# Sheet3.net
KiCad netlist of a schematic drawn in Altium Designer
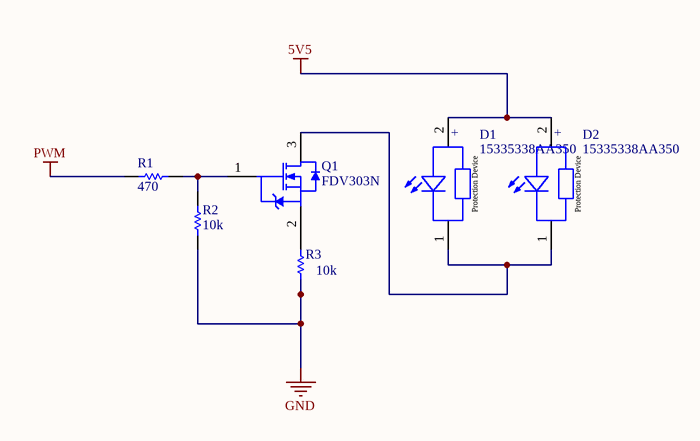
[diagram p0: Sheet3.SchDoc]

(export (version "E")
  (design (tool "Eeschema 10.0.6"))
  (components
    (comp (ref "D1")
      (value "15335338AA350")
      (footprint "WL-SUMW_3535 UV-A_L3.4W3.4H2.1")
      (description "15335338AA350 WL-SUMW SMT UltraViolet Ceramic Waterclear")
      (libsource (lib "Altium Content Vault") (part "WL-SUMW"))
    )
    (comp (ref "D2")
      (value "15335338AA350")
      (footprint "WL-SUMW_3535 UV-A_L3.4W3.4H2.1")
      (description "15335338AA350 WL-SUMW SMT UltraViolet Ceramic Waterclear")
      (libsource (lib "Altium Content Vault") (part "WL-SUMW"))
    )
    (comp (ref "Q1")
      (value "FDV303N")
      (footprint "FAIR-FDV303N-3_V")
      (fields (field (name "MANUFACTURER") "Fairchild"))
      (libsource (lib "Altium Content Vault") (part "NEMOS-GSD-3_D"))
    )
    (comp (ref "R1")
      (value "470")
      (footprint "RESC1609X50X30NL8T20")
      (description "Chip Resistor, 0 Ohm, Jumper, 100 mW, -55 to 155 degC, 0603 (1608 Metric), RoHS, Tape and Reel")
      (fields (field (name "MANUFACTURER") "Vishay Semiconductor"))
      (libsource (lib "Altium Content Vault") (part "RES-2"))
    )
    (comp (ref "R2")
      (value "10k")
      (footprint "RESC1609X50X30NL8T20")
      (description "Chip Resistor, 0 Ohm, Jumper, 100 mW, -55 to 155 degC, 0603 (1608 Metric), RoHS, Tape and Reel")
      (fields (field (name "MANUFACTURER") "Vishay Semiconductor"))
      (libsource (lib "Altium Content Vault") (part "RES-2"))
    )
    (comp (ref "R3")
      (value "10k")
      (footprint "RESC1609X50X30NL8T20")
      (description "Chip Resistor, 0 Ohm, Jumper, 100 mW, -55 to 155 degC, 0603 (1608 Metric), RoHS, Tape and Reel")
      (fields (field (name "MANUFACTURER") "Vishay Semiconductor"))
      (libsource (lib "Altium Content Vault") (part "RES-2"))
    )
  )
  (nets
    (net (code "1") (name "5V5") (class "Default")
      (node (ref "D1") (pin "2") (pinfunction "A_2") (pintype "passive"))
      (node (ref "D2") (pin "2") (pinfunction "A_2") (pintype "passive"))
    )
    (net (code "2") (name "GND") (class "Default")
      (node (ref "R2") (pin "1") (pinfunction "1_1") (pintype "passive"))
      (node (ref "R3") (pin "1") (pinfunction "1_1") (pintype "passive"))
    )
    (net (code "3") (name "Net-(D1-K)") (class "Default")
      (node (ref "D1") (pin "1") (pinfunction "K_1") (pintype "passive"))
      (node (ref "D2") (pin "1") (pinfunction "K_1") (pintype "passive"))
      (node (ref "Q1") (pin "3") (pinfunction "D_3") (pintype "passive"))
    )
    (net (code "4") (name "Net-(Q1-G)") (class "Default")
      (node (ref "Q1") (pin "1") (pinfunction "G_1") (pintype "passive"))
      (node (ref "R1") (pin "2") (pinfunction "2_2") (pintype "passive"))
      (node (ref "R2") (pin "2") (pinfunction "2_2") (pintype "passive"))
    )
    (net (code "5") (name "Net-(Q1-S)") (class "Default")
      (node (ref "Q1") (pin "2") (pinfunction "S_2") (pintype "passive"))
      (node (ref "R3") (pin "2") (pinfunction "2_2") (pintype "passive"))
    )
    (net (code "6") (name "PWM") (class "Default")
      (node (ref "R1") (pin "1") (pinfunction "1_1") (pintype "passive"))
    )
  )
)
